# LightSensorsButtons.net
KiCad netlist of a schematic drawn in Altium Designer
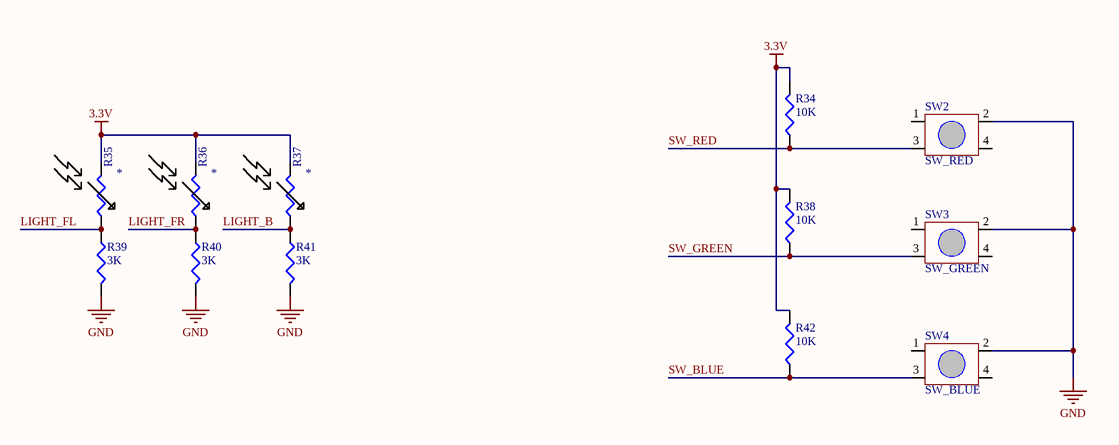
[diagram p0: LightSensorsButtons.SchDoc]

(export (version "E")
  (design (tool "Eeschema 10.0.6"))
  (components
    (comp (ref "R34")
      (value "10K")
      (footprint "RESC1608L")
      (description "Resistor")
      (fields (field (name "Comment") "Res3") (field (name "PUBLISHER") "Altium Limited"))
      (libsource (lib "Miscellaneous Devices") (part "Res3"))
    )
    (comp (ref "R35")
      (value "photoresistor")
      (footprint "photoresistor")
      (fields (field (name "ALTIUM_VALUE") "*"))
      (libsource (lib "mrone") (part "photoresistor"))
    )
    (comp (ref "R36")
      (value "photoresistor")
      (footprint "photoresistor")
      (fields (field (name "ALTIUM_VALUE") "*"))
      (libsource (lib "mrone") (part "photoresistor"))
    )
    (comp (ref "R37")
      (value "photoresistor")
      (footprint "photoresistor")
      (fields (field (name "ALTIUM_VALUE") "*"))
      (libsource (lib "mrone") (part "photoresistor"))
    )
    (comp (ref "R38")
      (value "10K")
      (footprint "RESC1608L")
      (description "Resistor")
      (fields (field (name "Comment") "Res3") (field (name "PUBLISHER") "Altium Limited"))
      (libsource (lib "Miscellaneous Devices") (part "Res3"))
    )
    (comp (ref "R39")
      (value "3K")
      (footprint "RESC1608L")
      (description "Resistor")
      (fields (field (name "Comment") "Res3") (field (name "PUBLISHER") "Altium Limited"))
      (libsource (lib "Miscellaneous Devices") (part "Res3"))
    )
    (comp (ref "R40")
      (value "3K")
      (footprint "RESC1608L")
      (description "Resistor")
      (fields (field (name "Comment") "Res3") (field (name "PUBLISHER") "Altium Limited"))
      (libsource (lib "Miscellaneous Devices") (part "Res3"))
    )
    (comp (ref "R41")
      (value "3K")
      (footprint "RESC1608L")
      (description "Resistor")
      (fields (field (name "Comment") "Res3") (field (name "PUBLISHER") "Altium Limited"))
      (libsource (lib "Miscellaneous Devices") (part "Res3"))
    )
    (comp (ref "R42")
      (value "10K")
      (footprint "RESC1608L")
      (description "Resistor")
      (fields (field (name "Comment") "Res3") (field (name "PUBLISHER") "Altium Limited"))
      (libsource (lib "Miscellaneous Devices") (part "Res3"))
    )
    (comp (ref "SW2")
      (value "SW_RED")
      (footprint "SwitchTall-TL330")
      (libsource (lib "mrone") (part "Switch-TL330"))
    )
    (comp (ref "SW3")
      (value "SW_GREEN")
      (footprint "SwitchTall-TL330")
      (libsource (lib "mrone") (part "Switch-TL330"))
    )
    (comp (ref "SW4")
      (value "SW_BLUE")
      (footprint "SwitchTall-TL330")
      (libsource (lib "mrone") (part "Switch-TL330"))
    )
  )
  (nets
    (net (code "1") (name "/LIGHT_B") (class "Default")
      (node (ref "R37") (pin "1") (pinfunction "1_1") (pintype "passive"))
      (node (ref "R41") (pin "1") (pinfunction "1_1") (pintype "passive"))
    )
    (net (code "2") (name "/LIGHT_FL") (class "Default")
      (node (ref "R35") (pin "1") (pinfunction "1_1") (pintype "passive"))
      (node (ref "R39") (pin "1") (pinfunction "1_1") (pintype "passive"))
    )
    (net (code "3") (name "/LIGHT_FR") (class "Default")
      (node (ref "R36") (pin "1") (pinfunction "1_1") (pintype "passive"))
      (node (ref "R40") (pin "1") (pinfunction "1_1") (pintype "passive"))
    )
    (net (code "4") (name "/SW_BLUE") (class "Default")
      (node (ref "R42") (pin "1") (pinfunction "1_1") (pintype "passive"))
      (node (ref "SW4") (pin "3") (pinfunction "3_3") (pintype "passive"))
    )
    (net (code "5") (name "/SW_GREEN") (class "Default")
      (node (ref "R38") (pin "1") (pinfunction "1_1") (pintype "passive"))
      (node (ref "SW3") (pin "3") (pinfunction "3_3") (pintype "passive"))
    )
    (net (code "6") (name "/SW_RED") (class "Default")
      (node (ref "R34") (pin "1") (pinfunction "1_1") (pintype "passive"))
      (node (ref "SW2") (pin "3") (pinfunction "3_3") (pintype "passive"))
    )
    (net (code "7") (name "3.3V") (class "Default")
      (node (ref "R34") (pin "2") (pinfunction "2_2") (pintype "passive"))
      (node (ref "R35") (pin "2") (pinfunction "2_2") (pintype "passive"))
      (node (ref "R36") (pin "2") (pinfunction "2_2") (pintype "passive"))
      (node (ref "R37") (pin "2") (pinfunction "2_2") (pintype "passive"))
      (node (ref "R38") (pin "2") (pinfunction "2_2") (pintype "passive"))
      (node (ref "R42") (pin "2") (pinfunction "2_2") (pintype "passive"))
    )
    (net (code "8") (name "GND") (class "Default")
      (node (ref "R39") (pin "2") (pinfunction "2_2") (pintype "passive"))
      (node (ref "R40") (pin "2") (pinfunction "2_2") (pintype "passive"))
      (node (ref "R41") (pin "2") (pinfunction "2_2") (pintype "passive"))
      (node (ref "SW2") (pin "2") (pinfunction "2_2") (pintype "passive"))
      (node (ref "SW3") (pin "2") (pinfunction "2_2") (pintype "passive"))
      (node (ref "SW4") (pin "2") (pinfunction "2_2") (pintype "passive"))
    )
    (net (code "9") (name "unconnected-(SW2-Pad1)") (class "Default")
      (node (ref "SW2") (pin "1") (pinfunction "1_1") (pintype "passive"))
    )
    (net (code "10") (name "unconnected-(SW2-Pad4)") (class "Default")
      (node (ref "SW2") (pin "4") (pinfunction "4_4") (pintype "passive"))
    )
    (net (code "11") (name "unconnected-(SW3-Pad1)") (class "Default")
      (node (ref "SW3") (pin "1") (pinfunction "1_1") (pintype "passive"))
    )
    (net (code "12") (name "unconnected-(SW3-Pad4)") (class "Default")
      (node (ref "SW3") (pin "4") (pinfunction "4_4") (pintype "passive"))
    )
    (net (code "13") (name "unconnected-(SW4-Pad1)") (class "Default")
      (node (ref "SW4") (pin "1") (pinfunction "1_1") (pintype "passive"))
    )
    (net (code "14") (name "unconnected-(SW4-Pad4)") (class "Default")
      (node (ref "SW4") (pin "4") (pinfunction "4_4") (pintype "passive"))
    )
  )
)
